# mc_board.net
KiCad netlist of a schematic drawn in EAGLE
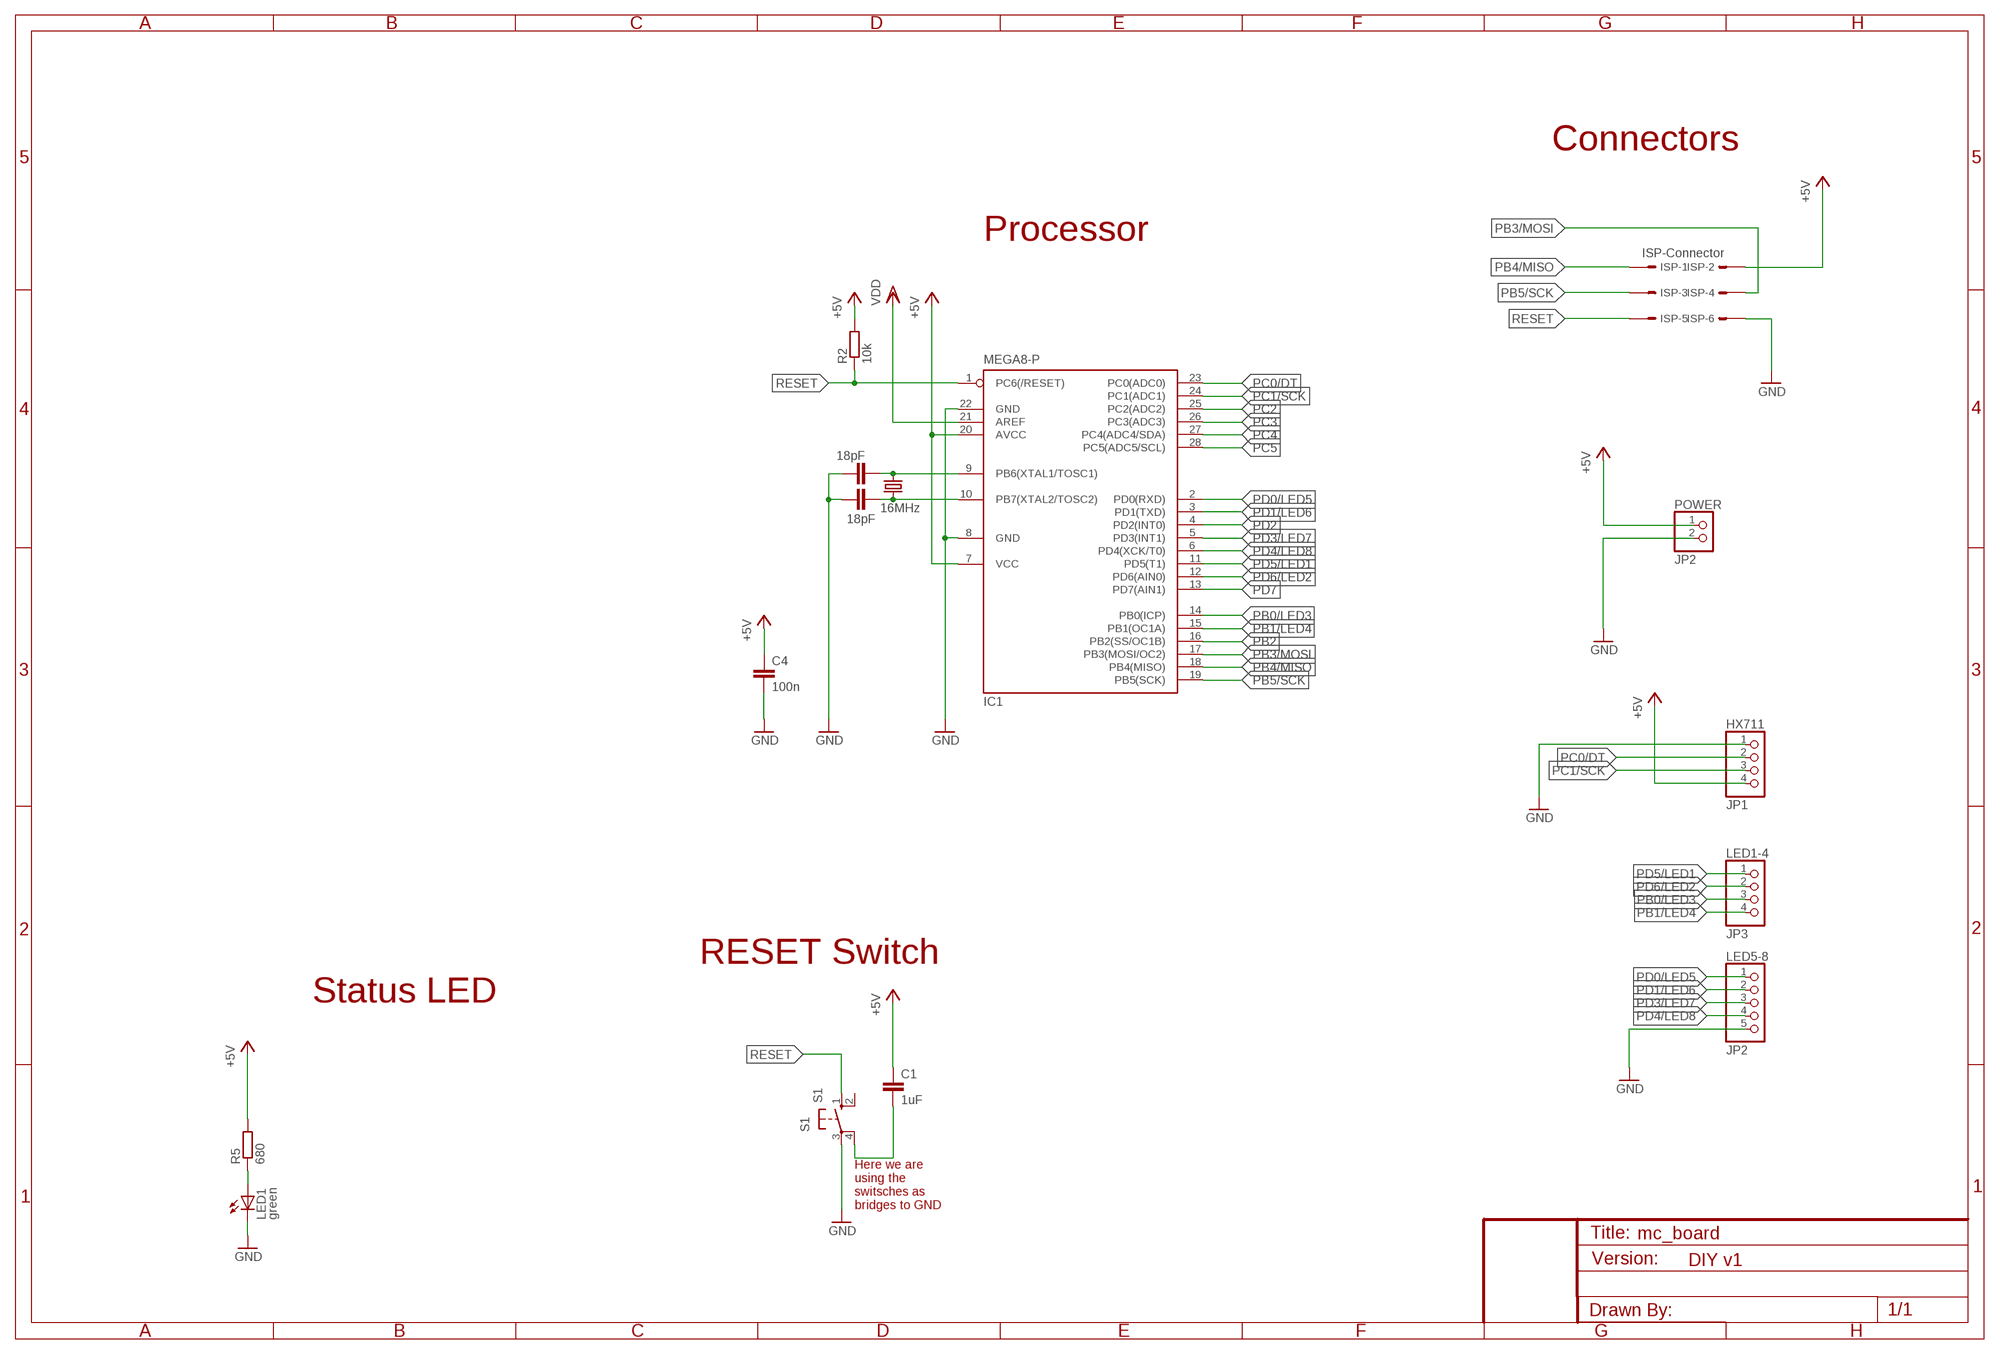
[diagram p0: schematic, sheet 1]

(export (version "E")
  (design (tool "Eeschema 10.0.6"))
  (components
    (comp (ref "C1")
      (value "1uF")
      (footprint "eagle-import:C0805")
      (libsource (lib "eagle-import") (part "C-EUC0805"))
    )
    (comp (ref "C2")
      (value "18pF")
      (footprint "eagle-import:C0805K")
      (libsource (lib "eagle-import") (part "resistor_C-EUC0805K"))
    )
    (comp (ref "C3")
      (value "18pF")
      (footprint "eagle-import:C0805K")
      (libsource (lib "eagle-import") (part "resistor_C-EUC0805K"))
    )
    (comp (ref "C4")
      (value "100n")
      (footprint "eagle-import:C0805")
      (libsource (lib "eagle-import") (part "C-EUC0805"))
    )
    (comp (ref "HX711")
      (value "JP1")
      (footprint "eagle-import:1X04")
      (libsource (lib "eagle-import") (part "PINHD-1X4"))
    )
    (comp (ref "IC1")
      (value "MEGA8-P")
      (footprint "eagle-import:DIL28-3")
      (libsource (lib "eagle-import") (part "MEGA8-P"))
    )
    (comp (ref "ISP")
      (value "ISP-Connector")
      (footprint "eagle-import:057-006-1")
      (libsource (lib "eagle-import") (part "057-006-1"))
    )
    (comp (ref "LED1")
      (value "green")
      (footprint "eagle-import:CHIPLED_0805")
      (libsource (lib "eagle-import") (part "LEDCHIPLED_0805"))
    )
    (comp (ref "LED1-4")
      (value "JP3")
      (footprint "eagle-import:1X04")
      (libsource (lib "eagle-import") (part "PINHD-1X4"))
    )
    (comp (ref "LED5-8")
      (value "JP2")
      (footprint "eagle-import:1X05")
      (libsource (lib "eagle-import") (part "PINHD-1X5"))
    )
    (comp (ref "POWER")
      (value "JP2")
      (footprint "eagle-import:1X02")
      (libsource (lib "eagle-import") (part "PINHD-1X2"))
    )
    (comp (ref "Q1")
      (value "16MHz")
      (footprint "eagle-import:HC49_S")
      (libsource (lib "eagle-import") (part "CRYSTALHC49S"))
    )
    (comp (ref "R2")
      (value "10k")
      (footprint "eagle-import:R1206")
      (libsource (lib "eagle-import") (part "R-EU_R1206"))
    )
    (comp (ref "R5")
      (value "680")
      (footprint "eagle-import:R0805")
      (libsource (lib "eagle-import") (part "R-EU_R0805"))
    )
    (comp (ref "S1")
      (value "S1")
      (footprint "eagle-import:B3F-10XX")
      (fields (field (name "MPN") "B3F-1000"))
      (libsource (lib "eagle-import") (part "10-XX"))
    )
  )
  (nets
    (net (code "1") (name "+5V") (class "Default")
      (node (ref "C1") (pin "1") (pinfunction "1_1") (pintype "passive"))
      (node (ref "C4") (pin "1") (pinfunction "1_1") (pintype "passive"))
      (node (ref "HX711") (pin "4") (pinfunction "4_4") (pintype "passive"))
      (node (ref "IC1") (pin "20") (pinfunction "AVCC_20") (pintype "power_in"))
      (node (ref "IC1") (pin "7") (pinfunction "VCC_7") (pintype "power_in"))
      (node (ref "ISP") (pin "2") (pinfunction "S_2") (pintype "passive"))
      (node (ref "POWER") (pin "1") (pinfunction "1_1") (pintype "passive"))
      (node (ref "R2") (pin "2") (pinfunction "2_2") (pintype "passive"))
      (node (ref "R5") (pin "2") (pinfunction "2_2") (pintype "passive"))
    )
    (net (code "2") (name "GND") (class "Default")
      (node (ref "C2") (pin "2") (pinfunction "2_2") (pintype "passive"))
      (node (ref "C3") (pin "2") (pinfunction "2_2") (pintype "passive"))
      (node (ref "C4") (pin "2") (pinfunction "2_2") (pintype "passive"))
      (node (ref "HX711") (pin "1") (pinfunction "1_1") (pintype "passive"))
      (node (ref "IC1") (pin "22") (pinfunction "GND_22") (pintype "power_in"))
      (node (ref "IC1") (pin "8") (pinfunction "GND_8") (pintype "power_in"))
      (node (ref "ISP") (pin "6") (pinfunction "S_6") (pintype "passive"))
      (node (ref "LED1") (pin "C") (pinfunction "C_C") (pintype "passive"))
      (node (ref "LED5-8") (pin "5") (pinfunction "5_5") (pintype "passive"))
      (node (ref "POWER") (pin "2") (pinfunction "2_2") (pintype "passive"))
      (node (ref "S1") (pin "3") (pinfunction "P_3") (pintype "passive"))
    )
    (net (code "3") (name "Net-(IC1-PB6(XTAL1{slash}TOSC1))") (class "Default")
      (node (ref "C3") (pin "1") (pinfunction "1_1") (pintype "passive"))
      (node (ref "IC1") (pin "9") (pinfunction "PB6(XTAL1/TOSC1)_9") (pintype "bidirectional"))
      (node (ref "Q1") (pin "1") (pinfunction "1_1") (pintype "passive"))
    )
    (net (code "4") (name "Net-(IC1-PB7(XTAL2{slash}TOSC2))") (class "Default")
      (node (ref "C2") (pin "1") (pinfunction "1_1") (pintype "passive"))
      (node (ref "IC1") (pin "10") (pinfunction "PB7(XTAL2/TOSC2)_10") (pintype "bidirectional"))
      (node (ref "Q1") (pin "2") (pinfunction "2_2") (pintype "passive"))
    )
    (net (code "5") (name "Net-(LED1-PadA)") (class "Default")
      (node (ref "LED1") (pin "A") (pinfunction "A_A") (pintype "passive"))
      (node (ref "R5") (pin "1") (pinfunction "1_1") (pintype "passive"))
    )
    (net (code "6") (name "Net-(S1-P1)") (class "Default")
      (node (ref "C1") (pin "2") (pinfunction "2_2") (pintype "passive"))
      (node (ref "S1") (pin "4") (pinfunction "P1_4") (pintype "passive"))
    )
    (net (code "7") (name "PB0{slash}LED3") (class "Default")
      (node (ref "IC1") (pin "14") (pinfunction "PB0(ICP)_14") (pintype "bidirectional"))
      (node (ref "LED1-4") (pin "3") (pinfunction "3_3") (pintype "passive"))
    )
    (net (code "8") (name "PB1{slash}LED4") (class "Default")
      (node (ref "IC1") (pin "15") (pinfunction "PB1(OC1A)_15") (pintype "bidirectional"))
      (node (ref "LED1-4") (pin "4") (pinfunction "4_4") (pintype "passive"))
    )
    (net (code "9") (name "PB2") (class "Default")
      (node (ref "IC1") (pin "16") (pinfunction "PB2(SS/OC1B)_16") (pintype "bidirectional"))
    )
    (net (code "10") (name "PB3{slash}MOSI") (class "Default")
      (node (ref "IC1") (pin "17") (pinfunction "PB3(MOSI/OC2)_17") (pintype "bidirectional"))
      (node (ref "ISP") (pin "4") (pinfunction "S_4") (pintype "passive"))
    )
    (net (code "11") (name "PB4{slash}MISO") (class "Default")
      (node (ref "IC1") (pin "18") (pinfunction "PB4(MISO)_18") (pintype "bidirectional"))
      (node (ref "ISP") (pin "1") (pinfunction "S_1") (pintype "passive"))
    )
    (net (code "12") (name "PB5{slash}SCK") (class "Default")
      (node (ref "IC1") (pin "19") (pinfunction "PB5(SCK)_19") (pintype "bidirectional"))
      (node (ref "ISP") (pin "3") (pinfunction "S_3") (pintype "passive"))
    )
    (net (code "13") (name "PC0{slash}DT") (class "Default")
      (node (ref "HX711") (pin "2") (pinfunction "2_2") (pintype "passive"))
      (node (ref "IC1") (pin "23") (pinfunction "PC0(ADC0)_23") (pintype "bidirectional"))
    )
    (net (code "14") (name "PC1{slash}SCK") (class "Default")
      (node (ref "HX711") (pin "3") (pinfunction "3_3") (pintype "passive"))
      (node (ref "IC1") (pin "24") (pinfunction "PC1(ADC1)_24") (pintype "bidirectional"))
    )
    (net (code "15") (name "PC2") (class "Default")
      (node (ref "IC1") (pin "25") (pinfunction "PC2(ADC2)_25") (pintype "bidirectional"))
    )
    (net (code "16") (name "PC3") (class "Default")
      (node (ref "IC1") (pin "26") (pinfunction "PC3(ADC3)_26") (pintype "bidirectional"))
    )
    (net (code "17") (name "PC4") (class "Default")
      (node (ref "IC1") (pin "27") (pinfunction "PC4(ADC4/SDA)_27") (pintype "bidirectional"))
    )
    (net (code "18") (name "PC5") (class "Default")
      (node (ref "IC1") (pin "28") (pinfunction "PC5(ADC5/SCL)_28") (pintype "bidirectional"))
    )
    (net (code "19") (name "PD0{slash}LED5") (class "Default")
      (node (ref "IC1") (pin "2") (pinfunction "PD0(RXD)_2") (pintype "bidirectional"))
      (node (ref "LED5-8") (pin "1") (pinfunction "1_1") (pintype "passive"))
    )
    (net (code "20") (name "PD1{slash}LED6") (class "Default")
      (node (ref "IC1") (pin "3") (pinfunction "PD1(TXD)_3") (pintype "bidirectional"))
      (node (ref "LED5-8") (pin "2") (pinfunction "2_2") (pintype "passive"))
    )
    (net (code "21") (name "PD2") (class "Default")
      (node (ref "IC1") (pin "4") (pinfunction "PD2(INT0)_4") (pintype "bidirectional"))
    )
    (net (code "22") (name "PD3{slash}LED7") (class "Default")
      (node (ref "IC1") (pin "5") (pinfunction "PD3(INT1)_5") (pintype "bidirectional"))
      (node (ref "LED5-8") (pin "3") (pinfunction "3_3") (pintype "passive"))
    )
    (net (code "23") (name "PD4{slash}LED8") (class "Default")
      (node (ref "IC1") (pin "6") (pinfunction "PD4(XCK/T0)_6") (pintype "bidirectional"))
      (node (ref "LED5-8") (pin "4") (pinfunction "4_4") (pintype "passive"))
    )
    (net (code "24") (name "PD5{slash}LED1") (class "Default")
      (node (ref "IC1") (pin "11") (pinfunction "PD5(T1)_11") (pintype "bidirectional"))
      (node (ref "LED1-4") (pin "1") (pinfunction "1_1") (pintype "passive"))
    )
    (net (code "25") (name "PD6{slash}LED2") (class "Default")
      (node (ref "IC1") (pin "12") (pinfunction "PD6(AIN0)_12") (pintype "bidirectional"))
      (node (ref "LED1-4") (pin "2") (pinfunction "2_2") (pintype "passive"))
    )
    (net (code "26") (name "PD7") (class "Default")
      (node (ref "IC1") (pin "13") (pinfunction "PD7(AIN1)_13") (pintype "bidirectional"))
    )
    (net (code "27") (name "RESET") (class "Default")
      (node (ref "IC1") (pin "1") (pinfunction "PC6(/RESET)_1") (pintype "bidirectional"))
      (node (ref "ISP") (pin "5") (pinfunction "S_5") (pintype "passive"))
      (node (ref "R2") (pin "1") (pinfunction "1_1") (pintype "passive"))
      (node (ref "S1") (pin "1") (pinfunction "S_1") (pintype "passive"))
    )
    (net (code "28") (name "VDD") (class "Default")
      (node (ref "IC1") (pin "21") (pinfunction "AREF_21") (pintype "passive"))
    )
    (net (code "29") (name "unconnected-(S1-S1-Pad2)") (class "Default")
      (node (ref "S1") (pin "2") (pinfunction "S1_2") (pintype "passive"))
    )
  )
)
